# v2.net
KiCad netlist of a schematic drawn in EAGLE
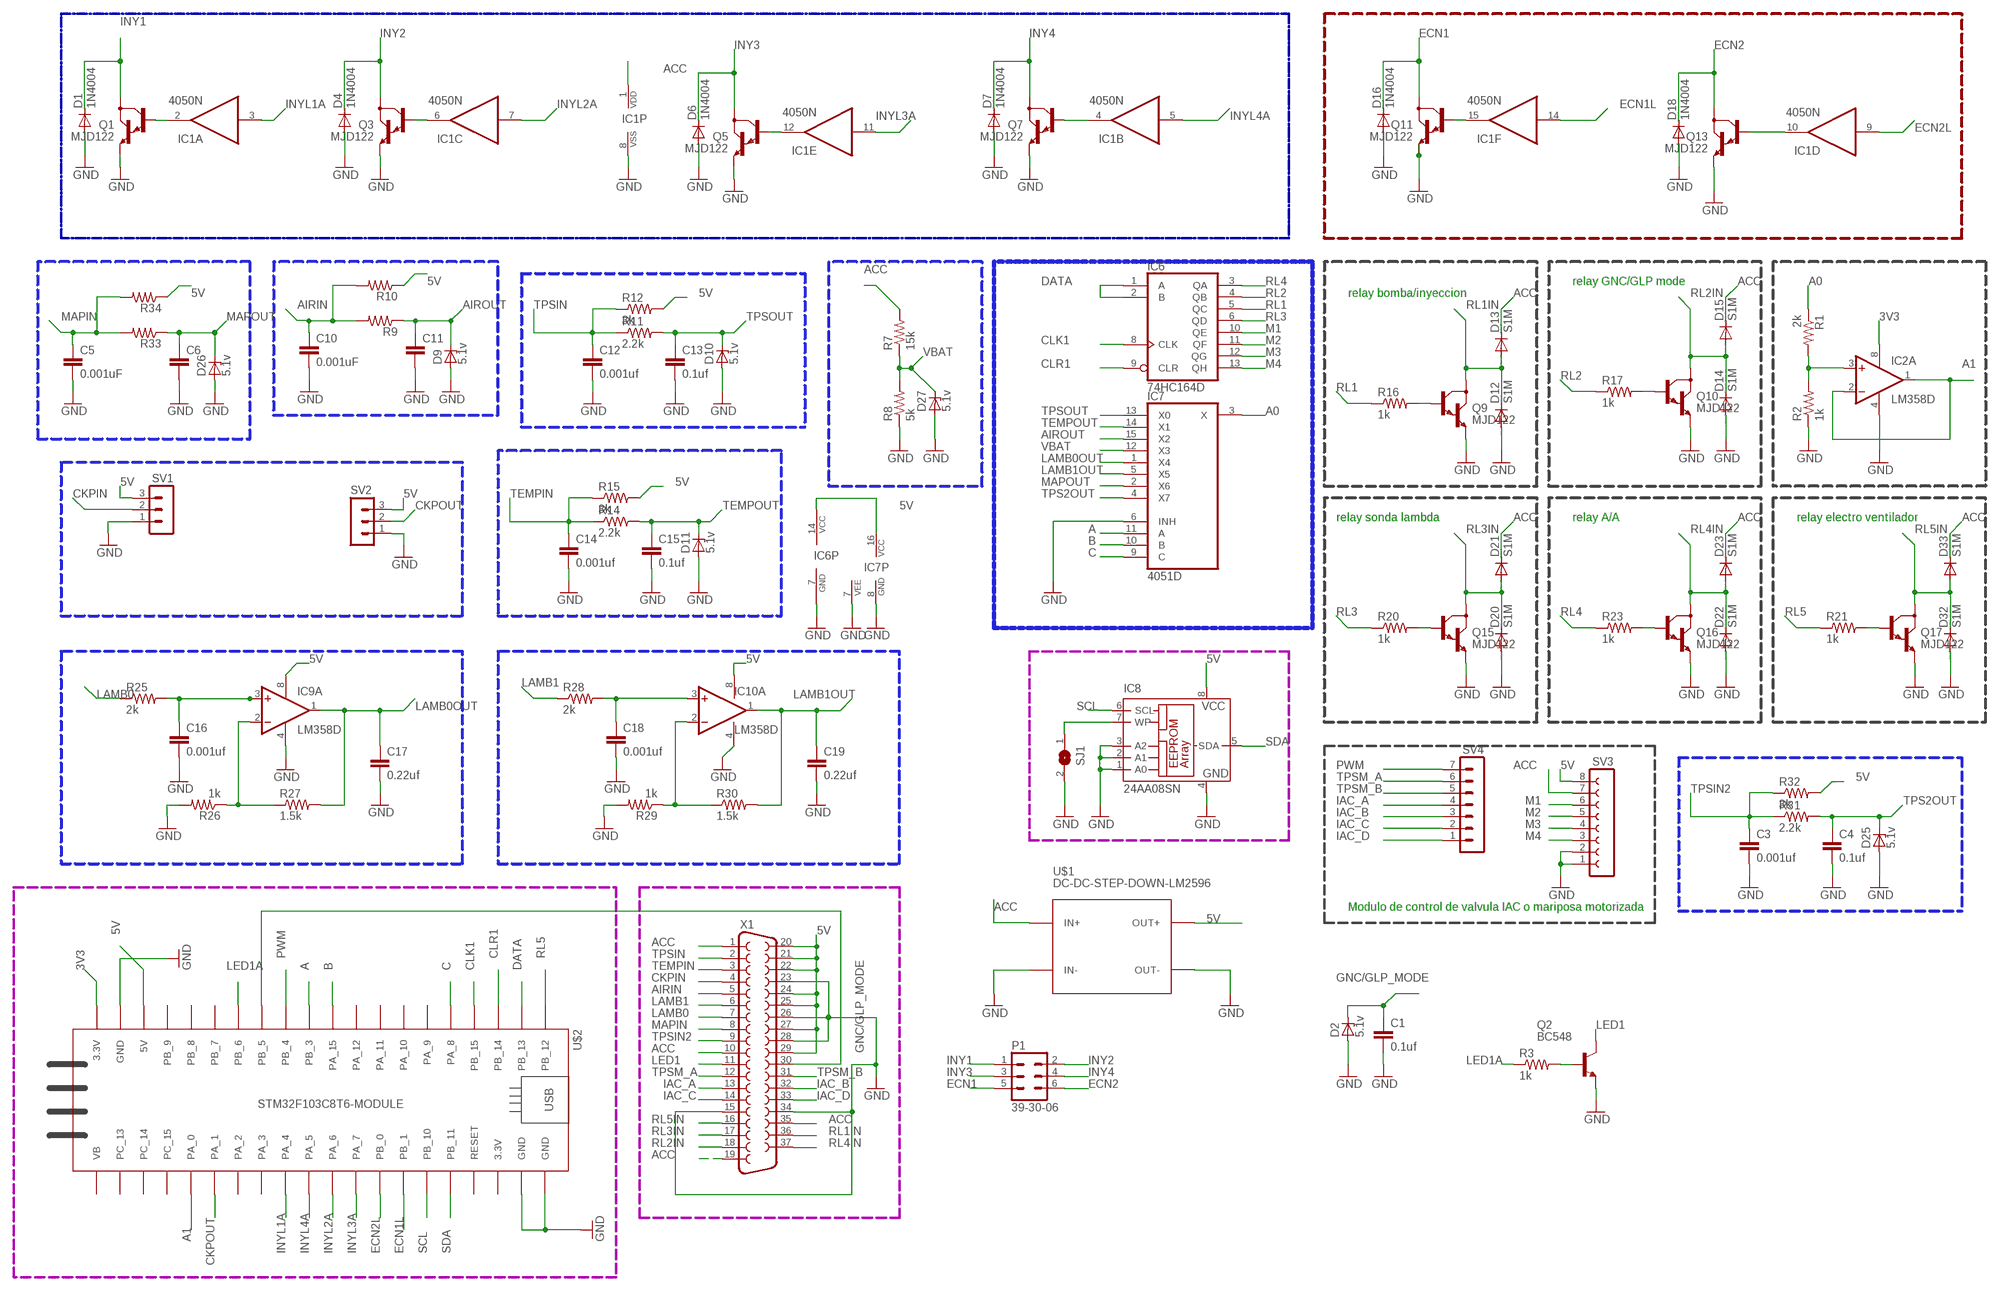
[diagram p0: schematic, sheet 1]

(export (version "E")
  (design (tool "Eeschema 10.0.6"))
  (components
    (comp (ref "C1")
      (value "0.1uf")
      (footprint "eagle-import:C025-025X050")
      (libsource (lib "eagle-import") (part "C-EU025-025X050"))
    )
    (comp (ref "C3")
      (value "0.001uf")
      (footprint "eagle-import:C025-025X050")
      (libsource (lib "eagle-import") (part "C-EU025-025X050"))
    )
    (comp (ref "C4")
      (value "0.1uf")
      (footprint "eagle-import:C025-025X050")
      (libsource (lib "eagle-import") (part "C-EU025-025X050"))
    )
    (comp (ref "C5")
      (value "0.001uF")
      (footprint "eagle-import:C025-025X050")
      (libsource (lib "eagle-import") (part "C-EU025-025X050"))
    )
    (comp (ref "C6")
      (value "C-EU025-025X050")
      (footprint "eagle-import:C025-025X050")
      (libsource (lib "eagle-import") (part "C-EU025-025X050"))
    )
    (comp (ref "C10")
      (value "0.001uF")
      (footprint "eagle-import:C025-025X050")
      (libsource (lib "eagle-import") (part "C-EU025-025X050"))
    )
    (comp (ref "C11")
      (value "C-EU025-025X050")
      (footprint "eagle-import:C025-025X050")
      (libsource (lib "eagle-import") (part "C-EU025-025X050"))
    )
    (comp (ref "C12")
      (value "0.001uf")
      (footprint "eagle-import:C025-025X050")
      (libsource (lib "eagle-import") (part "C-EU025-025X050"))
    )
    (comp (ref "C13")
      (value "0.1uf")
      (footprint "eagle-import:C025-025X050")
      (libsource (lib "eagle-import") (part "C-EU025-025X050"))
    )
    (comp (ref "C14")
      (value "0.001uf")
      (footprint "eagle-import:C025-025X050")
      (libsource (lib "eagle-import") (part "C-EU025-025X050"))
    )
    (comp (ref "C15")
      (value "0.1uf")
      (footprint "eagle-import:C025-025X050")
      (libsource (lib "eagle-import") (part "C-EU025-025X050"))
    )
    (comp (ref "C16")
      (value "0.001uf")
      (footprint "eagle-import:C025-025X050")
      (libsource (lib "eagle-import") (part "C-EU025-025X050"))
    )
    (comp (ref "C17")
      (value "0.22uf")
      (footprint "eagle-import:C025-025X050")
      (libsource (lib "eagle-import") (part "C-EU025-025X050"))
    )
    (comp (ref "C18")
      (value "0.001uf")
      (footprint "eagle-import:C025-025X050")
      (libsource (lib "eagle-import") (part "C-EU025-025X050"))
    )
    (comp (ref "C19")
      (value "0.22uf")
      (footprint "eagle-import:C025-025X050")
      (libsource (lib "eagle-import") (part "C-EU025-025X050"))
    )
    (comp (ref "D1")
      (value "1N4004")
      (footprint "eagle-import:DO41-10")
      (libsource (lib "eagle-import") (part "1N4004"))
    )
    (comp (ref "D2")
      (value "5.1v")
      (footprint "eagle-import:ZDIO-5")
      (libsource (lib "eagle-import") (part "ZENER-DIODEZD-5"))
    )
    (comp (ref "D4")
      (value "1N4004")
      (footprint "eagle-import:DO41-10")
      (libsource (lib "eagle-import") (part "1N4004"))
    )
    (comp (ref "D6")
      (value "1N4004")
      (footprint "eagle-import:DO41-10")
      (libsource (lib "eagle-import") (part "1N4004"))
    )
    (comp (ref "D7")
      (value "1N4004")
      (footprint "eagle-import:DO41-10")
      (libsource (lib "eagle-import") (part "1N4004"))
    )
    (comp (ref "D9")
      (value "5.1v")
      (footprint "eagle-import:ZDIO-5")
      (libsource (lib "eagle-import") (part "ZENER-DIODEZD-5"))
    )
    (comp (ref "D10")
      (value "5.1v")
      (footprint "eagle-import:ZDIO-5")
      (libsource (lib "eagle-import") (part "ZENER-DIODEZD-5"))
    )
    (comp (ref "D11")
      (value "5.1v")
      (footprint "eagle-import:ZDIO-5")
      (libsource (lib "eagle-import") (part "ZENER-DIODEZD-5"))
    )
    (comp (ref "D12")
      (value "S1M")
      (footprint "eagle-import:SMA")
      (libsource (lib "eagle-import") (part "S1M"))
    )
    (comp (ref "D13")
      (value "S1M")
      (footprint "eagle-import:SMA")
      (libsource (lib "eagle-import") (part "S1M"))
    )
    (comp (ref "D14")
      (value "S1M")
      (footprint "eagle-import:SMA")
      (libsource (lib "eagle-import") (part "S1M"))
    )
    (comp (ref "D15")
      (value "S1M")
      (footprint "eagle-import:SMA")
      (libsource (lib "eagle-import") (part "S1M"))
    )
    (comp (ref "D16")
      (value "1N4004")
      (footprint "eagle-import:DO41-10")
      (libsource (lib "eagle-import") (part "1N4004"))
    )
    (comp (ref "D18")
      (value "1N4004")
      (footprint "eagle-import:DO41-10")
      (libsource (lib "eagle-import") (part "1N4004"))
    )
    (comp (ref "D20")
      (value "S1M")
      (footprint "eagle-import:SMA")
      (libsource (lib "eagle-import") (part "S1M"))
    )
    (comp (ref "D21")
      (value "S1M")
      (footprint "eagle-import:SMA")
      (libsource (lib "eagle-import") (part "S1M"))
    )
    (comp (ref "D22")
      (value "S1M")
      (footprint "eagle-import:SMA")
      (libsource (lib "eagle-import") (part "S1M"))
    )
    (comp (ref "D23")
      (value "S1M")
      (footprint "eagle-import:SMA")
      (libsource (lib "eagle-import") (part "S1M"))
    )
    (comp (ref "D25")
      (value "5.1v")
      (footprint "eagle-import:ZDIO-5")
      (libsource (lib "eagle-import") (part "ZENER-DIODEZD-5"))
    )
    (comp (ref "D26")
      (value "5.1v")
      (footprint "eagle-import:ZDIO-5")
      (libsource (lib "eagle-import") (part "ZENER-DIODEZD-5"))
    )
    (comp (ref "D27")
      (value "5.1v")
      (footprint "eagle-import:ZDIO-5")
      (libsource (lib "eagle-import") (part "ZENER-DIODEZD-5"))
    )
    (comp (ref "D32")
      (value "S1M")
      (footprint "eagle-import:SMA")
      (libsource (lib "eagle-import") (part "S1M"))
    )
    (comp (ref "D33")
      (value "S1M")
      (footprint "eagle-import:SMA")
      (libsource (lib "eagle-import") (part "S1M"))
    )
    (comp (ref "IC1")
      (value "4050N")
      (footprint "eagle-import:DIL16")
      (libsource (lib "eagle-import") (part "4050N"))
    )
    (comp (ref "IC2")
      (value "LM358D")
      (footprint "eagle-import:SO08")
      (libsource (lib "eagle-import") (part "LM358D"))
    )
    (comp (ref "IC6")
      (value "74HC164D")
      (footprint "eagle-import:SO14")
      (libsource (lib "eagle-import") (part "74164DHC"))
    )
    (comp (ref "IC7")
      (value "4051D")
      (footprint "eagle-import:SO16")
      (libsource (lib "eagle-import") (part "4051D"))
    )
    (comp (ref "IC8")
      (value "24AA08SN")
      (footprint "eagle-import:SO-08")
      (fields (field (name "MF") "MICROCHIP") (field (name "MPN") "24AA08-I/SN"))
      (libsource (lib "eagle-import") (part "24SNAA08"))
    )
    (comp (ref "IC9")
      (value "LM358D")
      (footprint "eagle-import:SO08")
      (libsource (lib "eagle-import") (part "LM358D"))
    )
    (comp (ref "IC10")
      (value "LM358D")
      (footprint "eagle-import:SO08")
      (libsource (lib "eagle-import") (part "LM358D"))
    )
    (comp (ref "P1")
      (value "39-30-06")
      (footprint "eagle-import:39-30-_06_")
      (libsource (lib "eagle-import") (part "39-30-?06?"))
    )
    (comp (ref "Q1")
      (value "MJD122")
      (footprint "eagle-import:DPAK")
      (fields (field (name "MF") "STMicroelectronics"))
      (libsource (lib "eagle-import") (part "MJD122"))
    )
    (comp (ref "Q2")
      (value "BC548")
      (footprint "eagle-import:TO92-EBC")
      (libsource (lib "eagle-import") (part "BC548"))
    )
    (comp (ref "Q3")
      (value "MJD122")
      (footprint "eagle-import:DPAK")
      (fields (field (name "MF") "STMicroelectronics"))
      (libsource (lib "eagle-import") (part "MJD122"))
    )
    (comp (ref "Q5")
      (value "MJD122")
      (footprint "eagle-import:DPAK")
      (fields (field (name "MF") "STMicroelectronics"))
      (libsource (lib "eagle-import") (part "MJD122"))
    )
    (comp (ref "Q7")
      (value "MJD122")
      (footprint "eagle-import:DPAK")
      (fields (field (name "MF") "STMicroelectronics"))
      (libsource (lib "eagle-import") (part "MJD122"))
    )
    (comp (ref "Q9")
      (value "MJD122")
      (footprint "eagle-import:DPAK")
      (fields (field (name "MF") "STMicroelectronics"))
      (libsource (lib "eagle-import") (part "MJD122"))
    )
    (comp (ref "Q10")
      (value "MJD122")
      (footprint "eagle-import:DPAK")
      (fields (field (name "MF") "STMicroelectronics"))
      (libsource (lib "eagle-import") (part "MJD122"))
    )
    (comp (ref "Q11")
      (value "MJD122")
      (footprint "eagle-import:DPAK")
      (fields (field (name "MF") "STMicroelectronics"))
      (libsource (lib "eagle-import") (part "MJD122"))
    )
    (comp (ref "Q13")
      (value "MJD122")
      (footprint "eagle-import:DPAK")
      (fields (field (name "MF") "STMicroelectronics"))
      (libsource (lib "eagle-import") (part "MJD122"))
    )
    (comp (ref "Q15")
      (value "MJD122")
      (footprint "eagle-import:DPAK")
      (fields (field (name "MF") "STMicroelectronics"))
      (libsource (lib "eagle-import") (part "MJD122"))
    )
    (comp (ref "Q16")
      (value "MJD122")
      (footprint "eagle-import:DPAK")
      (fields (field (name "MF") "STMicroelectronics"))
      (libsource (lib "eagle-import") (part "MJD122"))
    )
    (comp (ref "Q17")
      (value "MJD122")
      (footprint "eagle-import:DPAK")
      (fields (field (name "MF") "STMicroelectronics"))
      (libsource (lib "eagle-import") (part "MJD122"))
    )
    (comp (ref "R1")
      (value "2k")
      (footprint "eagle-import:0204_5")
      (libsource (lib "eagle-import") (part "R-US_0204/5"))
    )
    (comp (ref "R2")
      (value "1k")
      (footprint "eagle-import:0204_5")
      (libsource (lib "eagle-import") (part "R-US_0204/5"))
    )
    (comp (ref "R3")
      (value "1k")
      (footprint "eagle-import:0204_5")
      (libsource (lib "eagle-import") (part "R-US_0204/5"))
    )
    (comp (ref "R7")
      (value "15k")
      (footprint "eagle-import:0204_5")
      (libsource (lib "eagle-import") (part "R-US_0204/5"))
    )
    (comp (ref "R8")
      (value "5k")
      (footprint "eagle-import:0204_5")
      (libsource (lib "eagle-import") (part "R-US_0204/5"))
    )
    (comp (ref "R9")
      (value "R-US_0204/5")
      (footprint "eagle-import:0204_5")
      (libsource (lib "eagle-import") (part "R-US_0204/5"))
    )
    (comp (ref "R10")
      (value "R-US_0204/5")
      (footprint "eagle-import:0204_5")
      (libsource (lib "eagle-import") (part "R-US_0204/5"))
    )
    (comp (ref "R11")
      (value "2.2k")
      (footprint "eagle-import:0204_5")
      (libsource (lib "eagle-import") (part "R-US_0204/5"))
    )
    (comp (ref "R12")
      (value "3k")
      (footprint "eagle-import:0204_5")
      (libsource (lib "eagle-import") (part "R-US_0204/5"))
    )
    (comp (ref "R14")
      (value "2.2k")
      (footprint "eagle-import:0204_5")
      (libsource (lib "eagle-import") (part "R-US_0204/5"))
    )
    (comp (ref "R15")
      (value "3k")
      (footprint "eagle-import:0204_5")
      (libsource (lib "eagle-import") (part "R-US_0204/5"))
    )
    (comp (ref "R16")
      (value "1k")
      (footprint "eagle-import:0204_5")
      (libsource (lib "eagle-import") (part "R-US_0204/5"))
    )
    (comp (ref "R17")
      (value "1k")
      (footprint "eagle-import:0204_5")
      (libsource (lib "eagle-import") (part "R-US_0204/5"))
    )
    (comp (ref "R20")
      (value "1k")
      (footprint "eagle-import:0204_5")
      (libsource (lib "eagle-import") (part "R-US_0204/5"))
    )
    (comp (ref "R21")
      (value "1k")
      (footprint "eagle-import:0204_5")
      (libsource (lib "eagle-import") (part "R-US_0204/5"))
    )
    (comp (ref "R23")
      (value "1k")
      (footprint "eagle-import:0204_5")
      (libsource (lib "eagle-import") (part "R-US_0204/5"))
    )
    (comp (ref "R25")
      (value "2k")
      (footprint "eagle-import:0204_5")
      (libsource (lib "eagle-import") (part "R-US_0204/5"))
    )
    (comp (ref "R26")
      (value "1k")
      (footprint "eagle-import:0204_5")
      (libsource (lib "eagle-import") (part "R-US_0204/5"))
    )
    (comp (ref "R27")
      (value "1.5k")
      (footprint "eagle-import:0204_5")
      (libsource (lib "eagle-import") (part "R-US_0204/5"))
    )
    (comp (ref "R28")
      (value "2k")
      (footprint "eagle-import:0204_5")
      (libsource (lib "eagle-import") (part "R-US_0204/5"))
    )
    (comp (ref "R29")
      (value "1k")
      (footprint "eagle-import:0204_5")
      (libsource (lib "eagle-import") (part "R-US_0204/5"))
    )
    (comp (ref "R30")
      (value "1.5k")
      (footprint "eagle-import:0204_5")
      (libsource (lib "eagle-import") (part "R-US_0204/5"))
    )
    (comp (ref "R31")
      (value "2.2k")
      (footprint "eagle-import:0204_5")
      (libsource (lib "eagle-import") (part "R-US_0204/5"))
    )
    (comp (ref "R32")
      (value "3k")
      (footprint "eagle-import:0204_5")
      (libsource (lib "eagle-import") (part "R-US_0204/5"))
    )
    (comp (ref "R33")
      (value "R-US_0204/5")
      (footprint "eagle-import:0204_5")
      (libsource (lib "eagle-import") (part "R-US_0204/5"))
    )
    (comp (ref "R34")
      (value "R-US_0204/5")
      (footprint "eagle-import:0204_5")
      (libsource (lib "eagle-import") (part "R-US_0204/5"))
    )
    (comp (ref "SJ1")
      (value "SJW")
      (footprint "eagle-import:SJW")
      (libsource (lib "eagle-import") (part "SJW"))
    )
    (comp (ref "SV1")
      (value "MA03-1")
      (footprint "eagle-import:MA03-1")
      (libsource (lib "eagle-import") (part "MA03-1"))
    )
    (comp (ref "SV2")
      (value "MA03-1")
      (footprint "eagle-import:MA03-1")
      (libsource (lib "eagle-import") (part "MA03-1"))
    )
    (comp (ref "SV3")
      (value "FE08-1")
      (footprint "eagle-import:FE08")
      (libsource (lib "eagle-import") (part "FE08-1"))
    )
    (comp (ref "SV4")
      (value "MA07-1")
      (footprint "eagle-import:MA07-1")
      (libsource (lib "eagle-import") (part "MA07-1"))
    )
    (comp (ref "U$1")
      (value "DC-DC-STEP-DOWN-LM2596")
      (footprint "eagle-import:DC-DC-STEP-DOWN-LM2596")
      (libsource (lib "eagle-import") (part "DC-DC-STEP-DOWN-LM2596"))
    )
    (comp (ref "U$2")
      (value "STM32F103C8T6-MODULE")
      (footprint "eagle-import:STM32F103C8T6-MODULE")
      (libsource (lib "eagle-import") (part "STM32F103C8T6-MODULE"))
    )
    (comp (ref "X1")
      (value "F37HP")
      (footprint "eagle-import:F37HP")
      (libsource (lib "eagle-import") (part "F37HP"))
    )
  )
  (nets
    (net (code "1") (name "/3V3") (class "Default")
      (node (ref "IC2") (pin "8") (pinfunction "V+_8") (pintype "power_in"))
      (node (ref "U$2") (pin "3.3V_1") (pinfunction "3.3V_3.3V_1") (pintype "bidirectional"))
    )
    (net (code "2") (name "/5V") (class "Default")
      (node (ref "IC10") (pin "8") (pinfunction "V+_8") (pintype "power_in"))
      (node (ref "IC6") (pin "14") (pinfunction "VCC_14") (pintype "power_in"))
      (node (ref "IC7") (pin "16") (pinfunction "VCC_16") (pintype "power_in"))
      (node (ref "IC8") (pin "8") (pinfunction "VCC_8") (pintype "power_in"))
      (node (ref "IC9") (pin "8") (pinfunction "V+_8") (pintype "power_in"))
      (node (ref "R10") (pin "1") (pinfunction "1_1") (pintype "passive"))
      (node (ref "R12") (pin "2") (pinfunction "2_2") (pintype "passive"))
      (node (ref "R15") (pin "2") (pinfunction "2_2") (pintype "passive"))
      (node (ref "R32") (pin "2") (pinfunction "2_2") (pintype "passive"))
      (node (ref "R34") (pin "1") (pinfunction "1_1") (pintype "passive"))
      (node (ref "SV1") (pin "3") (pinfunction "3_3") (pintype "passive"))
      (node (ref "SV2") (pin "3") (pinfunction "3_3") (pintype "passive"))
      (node (ref "SV3") (pin "8") (pinfunction "8_8") (pintype "passive"))
      (node (ref "U$1") (pin "OUT+") (pinfunction "OUT+_OUT+") (pintype "bidirectional"))
      (node (ref "U$2") (pin "5V") (pinfunction "5V_5V") (pintype "bidirectional"))
      (node (ref "X1") (pin "20") (pinfunction "20_20") (pintype "passive"))
      (node (ref "X1") (pin "21") (pinfunction "21_21") (pintype "passive"))
      (node (ref "X1") (pin "22") (pinfunction "22_22") (pintype "passive"))
      (node (ref "X1") (pin "24") (pinfunction "24_24") (pintype "passive"))
      (node (ref "X1") (pin "25") (pinfunction "25_25") (pintype "passive"))
      (node (ref "X1") (pin "27") (pinfunction "27_27") (pintype "passive"))
      (node (ref "X1") (pin "29") (pinfunction "29_29") (pintype "passive"))
    )
    (net (code "3") (name "/A") (class "Default")
      (node (ref "IC7") (pin "11") (pinfunction "A_11") (pintype "input"))
      (node (ref "U$2") (pin "PB_3") (pinfunction "PB_3_PB_3") (pintype "bidirectional"))
    )
    (net (code "4") (name "/A0") (class "Default")
      (node (ref "IC7") (pin "3") (pinfunction "X_3") (pintype "bidirectional"))
      (node (ref "R1") (pin "1") (pinfunction "1_1") (pintype "passive"))
    )
    (net (code "5") (name "/A1") (class "Default")
      (node (ref "IC2") (pin "1") (pinfunction "OUT_1") (pintype "output"))
      (node (ref "IC2") (pin "2") (pinfunction "-IN_2") (pintype "input"))
      (node (ref "U$2") (pin "PA_0") (pinfunction "PA_0_PA_0") (pintype "bidirectional"))
    )
    (net (code "6") (name "/ACC") (class "Default")
      (node (ref "D13") (pin "C") (pinfunction "C_C") (pintype "passive"))
      (node (ref "D15") (pin "C") (pinfunction "C_C") (pintype "passive"))
      (node (ref "D21") (pin "C") (pinfunction "C_C") (pintype "passive"))
      (node (ref "D23") (pin "C") (pinfunction "C_C") (pintype "passive"))
      (node (ref "D33") (pin "C") (pinfunction "C_C") (pintype "passive"))
      (node (ref "IC1") (pin "1") (pinfunction "VDD_1") (pintype "power_in"))
      (node (ref "R7") (pin "2") (pinfunction "2_2") (pintype "passive"))
      (node (ref "SV3") (pin "7") (pinfunction "7_7") (pintype "passive"))
      (node (ref "U$1") (pin "IN+") (pinfunction "IN+_IN+") (pintype "bidirectional"))
      (node (ref "X1") (pin "1") (pinfunction "1_1") (pintype "passive"))
      (node (ref "X1") (pin "10") (pinfunction "10_10") (pintype "passive"))
      (node (ref "X1") (pin "19") (pinfunction "19_19") (pintype "passive"))
      (node (ref "X1") (pin "35") (pinfunction "35_35") (pintype "passive"))
    )
    (net (code "7") (name "/AIRIN") (class "Default")
      (node (ref "C10") (pin "1") (pinfunction "1_1") (pintype "passive"))
      (node (ref "R10") (pin "2") (pinfunction "2_2") (pintype "passive"))
      (node (ref "R9") (pin "2") (pinfunction "2_2") (pintype "passive"))
      (node (ref "X1") (pin "5") (pinfunction "5_5") (pintype "passive"))
    )
    (net (code "8") (name "/AIROUT") (class "Default")
      (node (ref "C11") (pin "1") (pinfunction "1_1") (pintype "passive"))
      (node (ref "D9") (pin "C") (pinfunction "C_C") (pintype "passive"))
      (node (ref "IC7") (pin "15") (pinfunction "X2_15") (pintype "bidirectional"))
      (node (ref "R9") (pin "1") (pinfunction "1_1") (pintype "passive"))
    )
    (net (code "9") (name "/B") (class "Default")
      (node (ref "IC7") (pin "10") (pinfunction "B_10") (pintype "input"))
      (node (ref "U$2") (pin "PA_15") (pinfunction "PA_15_PA_15") (pintype "bidirectional"))
    )
    (net (code "10") (name "/C") (class "Default")
      (node (ref "IC7") (pin "9") (pinfunction "C_9") (pintype "input"))
      (node (ref "U$2") (pin "PA_8") (pinfunction "PA_8_PA_8") (pintype "bidirectional"))
    )
    (net (code "11") (name "/CKPIN") (class "Default")
      (node (ref "SV1") (pin "2") (pinfunction "2_2") (pintype "passive"))
      (node (ref "X1") (pin "4") (pinfunction "4_4") (pintype "passive"))
    )
    (net (code "12") (name "/CKPOUT") (class "Default")
      (node (ref "SV2") (pin "2") (pinfunction "2_2") (pintype "passive"))
      (node (ref "U$2") (pin "PA_1") (pinfunction "PA_1_PA_1") (pintype "bidirectional"))
    )
    (net (code "13") (name "/CLK1") (class "Default")
      (node (ref "IC6") (pin "8") (pinfunction "CLK_8") (pintype "input"))
      (node (ref "U$2") (pin "PB_15") (pinfunction "PB_15_PB_15") (pintype "bidirectional"))
    )
    (net (code "14") (name "/CLR1") (class "Default")
      (node (ref "IC6") (pin "9") (pinfunction "CLR_9") (pintype "input"))
      (node (ref "U$2") (pin "PB_14") (pinfunction "PB_14_PB_14") (pintype "bidirectional"))
    )
    (net (code "15") (name "/DATA") (class "Default")
      (node (ref "IC6") (pin "1") (pinfunction "A_1") (pintype "input"))
      (node (ref "IC6") (pin "2") (pinfunction "B_2") (pintype "input"))
      (node (ref "U$2") (pin "PB_13") (pinfunction "PB_13_PB_13") (pintype "bidirectional"))
    )
    (net (code "16") (name "/ECN1") (class "Default")
      (node (ref "D16") (pin "C") (pinfunction "C_C") (pintype "passive"))
      (node (ref "P1") (pin "5") (pinfunction "5_5") (pintype "passive"))
      (node (ref "Q11") (pin "4") (pinfunction "C_4") (pintype "passive"))
    )
    (net (code "17") (name "/ECN1L") (class "Default")
      (node (ref "IC1") (pin "14") (pinfunction "I_14") (pintype "input"))
      (node (ref "U$2") (pin "PB_1") (pinfunction "PB_1_PB_1") (pintype "bidirectional"))
    )
    (net (code "18") (name "/ECN2") (class "Default")
      (node (ref "D18") (pin "C") (pinfunction "C_C") (pintype "passive"))
      (node (ref "P1") (pin "6") (pinfunction "6_6") (pintype "passive"))
      (node (ref "Q13") (pin "4") (pinfunction "C_4") (pintype "passive"))
    )
    (net (code "19") (name "/ECN2L") (class "Default")
      (node (ref "IC1") (pin "9") (pinfunction "I_9") (pintype "input"))
      (node (ref "U$2") (pin "PB_0") (pinfunction "PB_0_PB_0") (pintype "bidirectional"))
    )
    (net (code "20") (name "/GNC{slash}GLP_MODE") (class "Default")
      (node (ref "C1") (pin "1") (pinfunction "1_1") (pintype "passive"))
      (node (ref "D2") (pin "C") (pinfunction "C_C") (pintype "passive"))
      (node (ref "U$2") (pin "PB_5") (pinfunction "PB_5_PB_5") (pintype "bidirectional"))
      (node (ref "X1") (pin "30") (pinfunction "30_30") (pintype "passive"))
    )
    (net (code "21") (name "/IAC_A") (class "Default")
      (node (ref "SV4") (pin "4") (pinfunction "4_4") (pintype "passive"))
      (node (ref "X1") (pin "13") (pinfunction "13_13") (pintype "passive"))
    )
    (net (code "22") (name "/IAC_B") (class "Default")
      (node (ref "SV4") (pin "3") (pinfunction "3_3") (pintype "passive"))
      (node (ref "X1") (pin "32") (pinfunction "32_32") (pintype "passive"))
    )
    (net (code "23") (name "/IAC_C") (class "Default")
      (node (ref "SV4") (pin "2") (pinfunction "2_2") (pintype "passive"))
      (node (ref "X1") (pin "14") (pinfunction "14_14") (pintype "passive"))
    )
    (net (code "24") (name "/IAC_D") (class "Default")
      (node (ref "SV4") (pin "1") (pinfunction "1_1") (pintype "passive"))
      (node (ref "X1") (pin "33") (pinfunction "33_33") (pintype "passive"))
    )
    (net (code "25") (name "/INY1") (class "Default")
      (node (ref "D1") (pin "C") (pinfunction "C_C") (pintype "passive"))
      (node (ref "P1") (pin "1") (pinfunction "1_1") (pintype "passive"))
      (node (ref "Q1") (pin "4") (pinfunction "C_4") (pintype "passive"))
    )
    (net (code "26") (name "/INY2") (class "Default")
      (node (ref "D4") (pin "C") (pinfunction "C_C") (pintype "passive"))
      (node (ref "P1") (pin "2") (pinfunction "2_2") (pintype "passive"))
      (node (ref "Q3") (pin "4") (pinfunction "C_4") (pintype "passive"))
    )
    (net (code "27") (name "/INY3") (class "Default")
      (node (ref "D6") (pin "C") (pinfunction "C_C") (pintype "passive"))
      (node (ref "P1") (pin "3") (pinfunction "3_3") (pintype "passive"))
      (node (ref "Q5") (pin "4") (pinfunction "C_4") (pintype "passive"))
    )
    (net (code "28") (name "/INY4") (class "Default")
      (node (ref "D7") (pin "C") (pinfunction "C_C") (pintype "passive"))
      (node (ref "P1") (pin "4") (pinfunction "4_4") (pintype "passive"))
      (node (ref "Q7") (pin "4") (pinfunction "C_4") (pintype "passive"))
    )
    (net (code "29") (name "/INYL1A") (class "Default")
      (node (ref "IC1") (pin "3") (pinfunction "I_3") (pintype "input"))
      (node (ref "U$2") (pin "PA_4") (pinfunction "PA_4_PA_4") (pintype "bidirectional"))
    )
    (net (code "30") (name "/INYL2A") (class "Default")
      (node (ref "IC1") (pin "7") (pinfunction "I_7") (pintype "input"))
      (node (ref "U$2") (pin "PA_6") (pinfunction "PA_6_PA_6") (pintype "bidirectional"))
    )
    (net (code "31") (name "/INYL3A") (class "Default")
      (node (ref "IC1") (pin "11") (pinfunction "I_11") (pintype "input"))
      (node (ref "U$2") (pin "PA_7") (pinfunction "PA_7_PA_7") (pintype "bidirectional"))
    )
    (net (code "32") (name "/INYL4A") (class "Default")
      (node (ref "IC1") (pin "5") (pinfunction "I_5") (pintype "input"))
      (node (ref "U$2") (pin "PA_5") (pinfunction "PA_5_PA_5") (pintype "bidirectional"))
    )
    (net (code "33") (name "/LAMB0") (class "Default")
      (node (ref "R25") (pin "1") (pinfunction "1_1") (pintype "passive"))
      (node (ref "X1") (pin "7") (pinfunction "7_7") (pintype "passive"))
    )
    (net (code "34") (name "/LAMB0OUT") (class "Default")
      (node (ref "C17") (pin "1") (pinfunction "1_1") (pintype "passive"))
      (node (ref "IC7") (pin "1") (pinfunction "X4_1") (pintype "bidirectional"))
      (node (ref "IC9") (pin "1") (pinfunction "OUT_1") (pintype "output"))
      (node (ref "R27") (pin "2") (pinfunction "2_2") (pintype "passive"))
    )
    (net (code "35") (name "/LAMB1") (class "Default")
      (node (ref "R28") (pin "1") (pinfunction "1_1") (pintype "passive"))
      (node (ref "X1") (pin "6") (pinfunction "6_6") (pintype "passive"))
    )
    (net (code "36") (name "/LAMB1OUT") (class "Default")
      (node (ref "C19") (pin "1") (pinfunction "1_1") (pintype "passive"))
      (node (ref "IC10") (pin "1") (pinfunction "OUT_1") (pintype "output"))
      (node (ref "IC7") (pin "5") (pinfunction "X5_5") (pintype "bidirectional"))
      (node (ref "R30") (pin "2") (pinfunction "2_2") (pintype "passive"))
    )
    (net (code "37") (name "/LED1") (class "Default")
      (node (ref "Q2") (pin "C") (pinfunction "C_C") (pintype "passive"))
      (node (ref "X1") (pin "11") (pinfunction "11_11") (pintype "passive"))
    )
    (net (code "38") (name "/LED1A") (class "Default")
      (node (ref "R3") (pin "1") (pinfunction "1_1") (pintype "passive"))
      (node (ref "U$2") (pin "PB_6") (pinfunction "PB_6_PB_6") (pintype "bidirectional"))
    )
    (net (code "39") (name "/M1") (class "Default")
      (node (ref "IC6") (pin "10") (pinfunction "QE_10") (pintype "output"))
      (node (ref "SV3") (pin "6") (pinfunction "6_6") (pintype "passive"))
    )
    (net (code "40") (name "/M2") (class "Default")
      (node (ref "IC6") (pin "11") (pinfunction "QF_11") (pintype "output"))
      (node (ref "SV3") (pin "5") (pinfunction "5_5") (pintype "passive"))
    )
    (net (code "41") (name "/M3") (class "Default")
      (node (ref "IC6") (pin "12") (pinfunction "QG_12") (pintype "output"))
      (node (ref "SV3") (pin "4") (pinfunction "4_4") (pintype "passive"))
    )
    (net (code "42") (name "/M4") (class "Default")
      (node (ref "IC6") (pin "13") (pinfunction "QH_13") (pintype "output"))
      (node (ref "SV3") (pin "3") (pinfunction "3_3") (pintype "passive"))
    )
    (net (code "43") (name "/MAPIN") (class "Default")
      (node (ref "C5") (pin "1") (pinfunction "1_1") (pintype "passive"))
      (node (ref "R33") (pin "2") (pinfunction "2_2") (pintype "passive"))
      (node (ref "R34") (pin "2") (pinfunction "2_2") (pintype "passive"))
      (node (ref "X1") (pin "8") (pinfunction "8_8") (pintype "passive"))
    )
    (net (code "44") (name "/MAPOUT") (class "Default")
      (node (ref "C6") (pin "1") (pinfunction "1_1") (pintype "passive"))
      (node (ref "D26") (pin "C") (pinfunction "C_C") (pintype "passive"))
      (node (ref "IC7") (pin "2") (pinfunction "X6_2") (pintype "bidirectional"))
      (node (ref "R33") (pin "1") (pinfunction "1_1") (pintype "passive"))
    )
    (net (code "45") (name "/PWM") (class "Default")
      (node (ref "SV4") (pin "7") (pinfunction "7_7") (pintype "passive"))
      (node (ref "U$2") (pin "PB_4") (pinfunction "PB_4_PB_4") (pintype "bidirectional"))
    )
    (net (code "46") (name "/RL1") (class "Default")
      (node (ref "IC6") (pin "5") (pinfunction "QC_5") (pintype "output"))
      (node (ref "R16") (pin "1") (pinfunction "1_1") (pintype "passive"))
    )
    (net (code "47") (name "/RL1IN") (class "Default")
      (node (ref "D12") (pin "C") (pinfunction "C_C") (pintype "passive"))
      (node (ref "D13") (pin "A") (pinfunction "A_A") (pintype "passive"))
      (node (ref "Q9") (pin "4") (pinfunction "C_4") (pintype "passive"))
      (node (ref "X1") (pin "36") (pinfunction "36_36") (pintype "passive"))
    )
    (net (code "48") (name "/RL2") (class "Default")
      (node (ref "IC6") (pin "4") (pinfunction "QB_4") (pintype "output"))
      (node (ref "R17") (pin "1") (pinfunction "1_1") (pintype "passive"))
    )
    (net (code "49") (name "/RL2IN") (class "Default")
      (node (ref "D14") (pin "C") (pinfunction "C_C") (pintype "passive"))
      (node (ref "D15") (pin "A") (pinfunction "A_A") (pintype "passive"))
      (node (ref "Q10") (pin "4") (pinfunction "C_4") (pintype "passive"))
      (node (ref "X1") (pin "18") (pinfunction "18_18") (pintype "passive"))
    )
    (net (code "50") (name "/RL3") (class "Default")
      (node (ref "IC6") (pin "6") (pinfunction "QD_6") (pintype "output"))
      (node (ref "R20") (pin "1") (pinfunction "1_1") (pintype "passive"))
    )
    (net (code "51") (name "/RL3IN") (class "Default")
      (node (ref "D20") (pin "C") (pinfunction "C_C") (pintype "passive"))
      (node (ref "D21") (pin "A") (pinfunction "A_A") (pintype "passive"))
      (node (ref "Q15") (pin "4") (pinfunction "C_4") (pintype "passive"))
      (node (ref "X1") (pin "17") (pinfunction "17_17") (pintype "passive"))
    )
    (net (code "52") (name "/RL4") (class "Default")
      (node (ref "IC6") (pin "3") (pinfunction "QA_3") (pintype "output"))
      (node (ref "R23") (pin "1") (pinfunction "1_1") (pintype "passive"))
    )
    (net (code "53") (name "/RL4IN") (class "Default")
      (node (ref "D22") (pin "C") (pinfunction "C_C") (pintype "passive"))
      (node (ref "D23") (pin "A") (pinfunction "A_A") (pintype "passive"))
      (node (ref "Q16") (pin "4") (pinfunction "C_4") (pintype "passive"))
      (node (ref "X1") (pin "37") (pinfunction "37_37") (pintype "passive"))
    )
    (net (code "54") (name "/RL5") (class "Default")
      (node (ref "R21") (pin "1") (pinfunction "1_1") (pintype "passive"))
      (node (ref "U$2") (pin "PB_12") (pinfunction "PB_12_PB_12") (pintype "bidirectional"))
    )
    (net (code "55") (name "/RL5IN") (class "Default")
      (node (ref "D32") (pin "C") (pinfunction "C_C") (pintype "passive"))
      (node (ref "D33") (pin "A") (pinfunction "A_A") (pintype "passive"))
      (node (ref "Q17") (pin "4") (pinfunction "C_4") (pintype "passive"))
      (node (ref "X1") (pin "16") (pinfunction "16_16") (pintype "passive"))
    )
    (net (code "56") (name "/SCL") (class "Default")
      (node (ref "IC8") (pin "6") (pinfunction "SCL_6") (pintype "input"))
      (node (ref "U$2") (pin "PB_10") (pinfunction "PB_10_PB_10") (pintype "bidirectional"))
    )
    (net (code "57") (name "/SDA") (class "Default")
      (node (ref "IC8") (pin "5") (pinfunction "SDA_5") (pintype "bidirectional"))
      (node (ref "U$2") (pin "PB_11") (pinfunction "PB_11_PB_11") (pintype "bidirectional"))
    )
    (net (code "58") (name "/TEMPIN") (class "Default")
      (node (ref "C14") (pin "1") (pinfunction "1_1") (pintype "passive"))
      (node (ref "R14") (pin "1") (pinfunction "1_1") (pintype "passive"))
      (node (ref "R15") (pin "1") (pinfunction "1_1") (pintype "passive"))
      (node (ref "X1") (pin "3") (pinfunction "3_3") (pintype "passive"))
    )
    (net (code "59") (name "/TEMPOUT") (class "Default")
      (node (ref "C15") (pin "1") (pinfunction "1_1") (pintype "passive"))
      (node (ref "D11") (pin "C") (pinfunction "C_C") (pintype "passive"))
      (node (ref "IC7") (pin "14") (pinfunction "X1_14") (pintype "bidirectional"))
      (node (ref "R14") (pin "2") (pinfunction "2_2") (pintype "passive"))
    )
    (net (code "60") (name "/TPS2OUT") (class "Default")
      (node (ref "C4") (pin "1") (pinfunction "1_1") (pintype "passive"))
      (node (ref "D25") (pin "C") (pinfunction "C_C") (pintype "passive"))
      (node (ref "IC7") (pin "4") (pinfunction "X7_4") (pintype "bidirectional"))
      (node (ref "R31") (pin "2") (pinfunction "2_2") (pintype "passive"))
    )
    (net (code "61") (name "/TPSIN") (class "Default")
      (node (ref "C12") (pin "1") (pinfunction "1_1") (pintype "passive"))
      (node (ref "R11") (pin "1") (pinfunction "1_1") (pintype "passive"))
      (node (ref "R12") (pin "1") (pinfunction "1_1") (pintype "passive"))
      (node (ref "X1") (pin "2") (pinfunction "2_2") (pintype "passive"))
    )
    (net (code "62") (name "/TPSIN2") (class "Default")
      (node (ref "C3") (pin "1") (pinfunction "1_1") (pintype "passive"))
      (node (ref "R31") (pin "1") (pinfunction "1_1") (pintype "passive"))
      (node (ref "R32") (pin "1") (pinfunction "1_1") (pintype "passive"))
      (node (ref "X1") (pin "9") (pinfunction "9_9") (pintype "passive"))
    )
    (net (code "63") (name "/TPSM_A") (class "Default")
      (node (ref "SV4") (pin "6") (pinfunction "6_6") (pintype "passive"))
      (node (ref "X1") (pin "12") (pinfunction "12_12") (pintype "passive"))
    )
    (net (code "64") (name "/TPSM_B") (class "Default")
      (node (ref "SV4") (pin "5") (pinfunction "5_5") (pintype "passive"))
      (node (ref "X1") (pin "31") (pinfunction "31_31") (pintype "passive"))
    )
    (net (code "65") (name "/TPSOUT") (class "Default")
      (node (ref "C13") (pin "1") (pinfunction "1_1") (pintype "passive"))
      (node (ref "D10") (pin "C") (pinfunction "C_C") (pintype "passive"))
      (node (ref "IC7") (pin "13") (pinfunction "X0_13") (pintype "bidirectional"))
      (node (ref "R11") (pin "2") (pinfunction "2_2") (pintype "passive"))
    )
    (net (code "66") (name "/VBAT") (class "Default")
      (node (ref "D27") (pin "C") (pinfunction "C_C") (pintype "passive"))
      (node (ref "IC7") (pin "12") (pinfunction "X3_12") (pintype "bidirectional"))
      (node (ref "R7") (pin "1") (pinfunction "1_1") (pintype "passive"))
      (node (ref "R8") (pin "2") (pinfunction "2_2") (pintype "passive"))
    )
    (net (code "67") (name "GND") (class "Default")
      (node (ref "C1") (pin "2") (pinfunction "2_2") (pintype "passive"))
      (node (ref "C10") (pin "2") (pinfunction "2_2") (pintype "passive"))
      (node (ref "C11") (pin "2") (pinfunction "2_2") (pintype "passive"))
      (node (ref "C12") (pin "2") (pinfunction "2_2") (pintype "passive"))
      (node (ref "C13") (pin "2") (pinfunction "2_2") (pintype "passive"))
      (node (ref "C14") (pin "2") (pinfunction "2_2") (pintype "passive"))
      (node (ref "C15") (pin "2") (pinfunction "2_2") (pintype "passive"))
      (node (ref "C16") (pin "2") (pinfunction "2_2") (pintype "passive"))
      (node (ref "C17") (pin "2") (pinfunction "2_2") (pintype "passive"))
      (node (ref "C18") (pin "2") (pinfunction "2_2") (pintype "passive"))
      (node (ref "C19") (pin "2") (pinfunction "2_2") (pintype "passive"))
      (node (ref "C3") (pin "2") (pinfunction "2_2") (pintype "passive"))
      (node (ref "C4") (pin "2") (pinfunction "2_2") (pintype "passive"))
      (node (ref "C5") (pin "2") (pinfunction "2_2") (pintype "passive"))
      (node (ref "C6") (pin "2") (pinfunction "2_2") (pintype "passive"))
      (node (ref "D1") (pin "A") (pinfunction "A_A") (pintype "passive"))
      (node (ref "D10") (pin "A") (pinfunction "A_A") (pintype "passive"))
      (node (ref "D11") (pin "A") (pinfunction "A_A") (pintype "passive"))
      (node (ref "D12") (pin "A") (pinfunction "A_A") (pintype "passive"))
      (node (ref "D14") (pin "A") (pinfunction "A_A") (pintype "passive"))
      (node (ref "D16") (pin "A") (pinfunction "A_A") (pintype "passive"))
      (node (ref "D18") (pin "A") (pinfunction "A_A") (pintype "passive"))
      (node (ref "D2") (pin "A") (pinfunction "A_A") (pintype "passive"))
      (node (ref "D20") (pin "A") (pinfunction "A_A") (pintype "passive"))
      (node (ref "D22") (pin "A") (pinfunction "A_A") (pintype "passive"))
      (node (ref "D25") (pin "A") (pinfunction "A_A") (pintype "passive"))
      (node (ref "D26") (pin "A") (pinfunction "A_A") (pintype "passive"))
      (node (ref "D27") (pin "A") (pinfunction "A_A") (pintype "passive"))
      (node (ref "D32") (pin "A") (pinfunction "A_A") (pintype "passive"))
      (node (ref "D4") (pin "A") (pinfunction "A_A") (pintype "passive"))
      (node (ref "D6") (pin "A") (pinfunction "A_A") (pintype "passive"))
      (node (ref "D7") (pin "A") (pinfunction "A_A") (pintype "passive"))
      (node (ref "D9") (pin "A") (pinfunction "A_A") (pintype "passive"))
      (node (ref "IC1") (pin "8") (pinfunction "VSS_8") (pintype "power_in"))
      (node (ref "IC10") (pin "4") (pinfunction "V-_4") (pintype "power_in"))
      (node (ref "IC2") (pin "4") (pinfunction "V-_4") (pintype "power_in"))
      (node (ref "IC6") (pin "7") (pinfunction "GND_7") (pintype "power_in"))
      (node (ref "IC7") (pin "6") (pinfunction "INH_6") (pintype "input"))
      (node (ref "IC7") (pin "7") (pinfunction "VEE_7") (pintype "power_in"))
      (node (ref "IC7") (pin "8") (pinfunction "GND_8") (pintype "power_in"))
      (node (ref "IC8") (pin "1") (pinfunction "A0_1") (pintype "input"))
      (node (ref "IC8") (pin "2") (pinfunction "A1_2") (pintype "input"))
      (node (ref "IC8") (pin "3") (pinfunction "A2_3") (pintype "input"))
      (node (ref "IC8") (pin "4") (pinfunction "GND_4") (pintype "power_in"))
      (node (ref "IC9") (pin "4") (pinfunction "V-_4") (pintype "power_in"))
      (node (ref "Q1") (pin "3") (pinfunction "E_3") (pintype "passive"))
      (node (ref "Q10") (pin "3") (pinfunction "E_3") (pintype "passive"))
      (node (ref "Q11") (pin "3") (pinfunction "E_3") (pintype "passive"))
      (node (ref "Q13") (pin "3") (pinfunction "E_3") (pintype "passive"))
      (node (ref "Q15") (pin "3") (pinfunction "E_3") (pintype "passive"))
      (node (ref "Q16") (pin "3") (pinfunction "E_3") (pintype "passive"))
      (node (ref "Q17") (pin "3") (pinfunction "E_3") (pintype "passive"))
      (node (ref "Q2") (pin "E") (pinfunction "E_E") (pintype "passive"))
      (node (ref "Q3") (pin "3") (pinfunction "E_3") (pintype "passive"))
      (node (ref "Q5") (pin "3") (pinfunction "E_3") (pintype "passive"))
      (node (ref "Q7") (pin "3") (pinfunction "E_3") (pintype "passive"))
      (node (ref "Q9") (pin "3") (pinfunction "E_3") (pintype "passive"))
      (node (ref "R2") (pin "1") (pinfunction "1_1") (pintype "passive"))
      (node (ref "R26") (pin "2") (pinfunction "2_2") (pintype "passive"))
      (node (ref "R29") (pin "2") (pinfunction "2_2") (pintype "passive"))
      (node (ref "R8") (pin "1") (pinfunction "1_1") (pintype "passive"))
      (node (ref "SJ1") (pin "2") (pinfunction "2_2") (pintype "passive"))
      (node (ref "SV1") (pin "1") (pinfunction "1_1") (pintype "passive"))
      (node (ref "SV2") (pin "1") (pinfunction "1_1") (pintype "passive"))
      (node (ref "SV3") (pin "1") (pinfunction "1_1") (pintype "passive"))
      (node (ref "SV3") (pin "2") (pinfunction "2_2") (pintype "passive"))
      (node (ref "U$1") (pin "IN-") (pinfunction "IN-_IN-") (pintype "bidirectional"))
      (node (ref "U$1") (pin "OUT-") (pinfunction "OUT-_OUT-") (pintype "bidirectional"))
      (node (ref "U$2") (pin "GND_1") (pinfunction "GND_GND_1") (pintype "bidirectional"))
      (node (ref "U$2") (pin "GND_2") (pinfunction "GND_GND_2") (pintype "bidirectional"))
      (node (ref "U$2") (pin "GND_3") (pinfunction "GND_GND_3") (pintype "power_in"))
      (node (ref "X1") (pin "15") (pinfunction "15_15") (pintype "passive"))
      (node (ref "X1") (pin "23") (pinfunction "23_23") (pintype "passive"))
      (node (ref "X1") (pin "26") (pinfunction "26_26") (pintype "passive"))
      (node (ref "X1") (pin "28") (pinfunction "28_28") (pintype "passive"))
      (node (ref "X1") (pin "34") (pinfunction "34_34") (pintype "passive"))
    )
    (net (code "68") (name "Net-(IC1A-O)") (class "Default")
      (node (ref "IC1") (pin "2") (pinfunction "O_2") (pintype "output"))
      (node (ref "Q1") (pin "1") (pinfunction "B_1") (pintype "passive"))
    )
    (net (code "69") (name "Net-(IC1B-O)") (class "Default")
      (node (ref "IC1") (pin "4") (pinfunction "O_4") (pintype "output"))
      (node (ref "Q7") (pin "1") (pinfunction "B_1") (pintype "passive"))
    )
    (net (code "70") (name "Net-(IC1C-O)") (class "Default")
      (node (ref "IC1") (pin "6") (pinfunction "O_6") (pintype "output"))
      (node (ref "Q3") (pin "1") (pinfunction "B_1") (pintype "passive"))
    )
    (net (code "71") (name "Net-(IC1D-O)") (class "Default")
      (node (ref "IC1") (pin "10") (pinfunction "O_10") (pintype "output"))
      (node (ref "Q13") (pin "1") (pinfunction "B_1") (pintype "passive"))
    )
    (net (code "72") (name "Net-(IC1E-O)") (class "Default")
      (node (ref "IC1") (pin "12") (pinfunction "O_12") (pintype "output"))
      (node (ref "Q5") (pin "1") (pinfunction "B_1") (pintype "passive"))
    )
    (net (code "73") (name "Net-(IC1F-O)") (class "Default")
      (node (ref "IC1") (pin "15") (pinfunction "O_15") (pintype "output"))
      (node (ref "Q11") (pin "1") (pinfunction "B_1") (pintype "passive"))
    )
    (net (code "74") (name "Net-(IC2A-+IN)") (class "Default")
      (node (ref "IC2") (pin "3") (pinfunction "+IN_3") (pintype "input"))
      (node (ref "R1") (pin "2") (pinfunction "2_2") (pintype "passive"))
      (node (ref "R2") (pin "2") (pinfunction "2_2") (pintype "passive"))
    )
    (net (code "75") (name "Net-(IC8-WP)") (class "Default")
      (node (ref "IC8") (pin "7") (pinfunction "WP_7") (pintype "input"))
      (node (ref "SJ1") (pin "1") (pinfunction "1_1") (pintype "passive"))
    )
    (net (code "76") (name "Net-(IC9A-+IN)") (class "Default")
      (node (ref "C16") (pin "1") (pinfunction "1_1") (pintype "passive"))
      (node (ref "IC9") (pin "3") (pinfunction "+IN_3") (pintype "input"))
      (node (ref "R25") (pin "2") (pinfunction "2_2") (pintype "passive"))
    )
    (net (code "77") (name "Net-(IC9A--IN)") (class "Default")
      (node (ref "IC9") (pin "2") (pinfunction "-IN_2") (pintype "input"))
      (node (ref "R26") (pin "1") (pinfunction "1_1") (pintype "passive"))
      (node (ref "R27") (pin "1") (pinfunction "1_1") (pintype "passive"))
    )
    (net (code "78") (name "Net-(IC10A-+IN)") (class "Default")
      (node (ref "C18") (pin "1") (pinfunction "1_1") (pintype "passive"))
      (node (ref "IC10") (pin "3") (pinfunction "+IN_3") (pintype "input"))
      (node (ref "R28") (pin "2") (pinfunction "2_2") (pintype "passive"))
    )
    (net (code "79") (name "Net-(IC10A--IN)") (class "Default")
      (node (ref "IC10") (pin "2") (pinfunction "-IN_2") (pintype "input"))
      (node (ref "R29") (pin "1") (pinfunction "1_1") (pintype "passive"))
      (node (ref "R30") (pin "1") (pinfunction "1_1") (pintype "passive"))
    )
    (net (code "80") (name "Net-(Q2-PadB)") (class "Default")
      (node (ref "Q2") (pin "B") (pinfunction "B_B") (pintype "passive"))
      (node (ref "R3") (pin "2") (pinfunction "2_2") (pintype "passive"))
    )
    (net (code "81") (name "Net-(Q9-B)") (class "Default")
      (node (ref "Q9") (pin "1") (pinfunction "B_1") (pintype "passive"))
      (node (ref "R16") (pin "2") (pinfunction "2_2") (pintype "passive"))
    )
    (net (code "82") (name "Net-(Q10-B)") (class "Default")
      (node (ref "Q10") (pin "1") (pinfunction "B_1") (pintype "passive"))
      (node (ref "R17") (pin "2") (pinfunction "2_2") (pintype "passive"))
    )
    (net (code "83") (name "Net-(Q15-B)") (class "Default")
      (node (ref "Q15") (pin "1") (pinfunction "B_1") (pintype "passive"))
      (node (ref "R20") (pin "2") (pinfunction "2_2") (pintype "passive"))
    )
    (net (code "84") (name "Net-(Q16-B)") (class "Default")
      (node (ref "Q16") (pin "1") (pinfunction "B_1") (pintype "passive"))
      (node (ref "R23") (pin "2") (pinfunction "2_2") (pintype "passive"))
    )
    (net (code "85") (name "Net-(Q17-B)") (class "Default")
      (node (ref "Q17") (pin "1") (pinfunction "B_1") (pintype "passive"))
      (node (ref "R21") (pin "2") (pinfunction "2_2") (pintype "passive"))
    )
    (net (code "86") (name "unconnected-(U$2-3.3V-Pad3.3V_2)") (class "Default")
      (node (ref "U$2") (pin "3.3V_2") (pinfunction "3.3V_3.3V_2") (pintype "bidirectional"))
    )
    (net (code "87") (name "unconnected-(U$2-PadPA_2)") (class "Default")
      (node (ref "U$2") (pin "PA_2") (pinfunction "PA_2_PA_2") (pintype "bidirectional"))
    )
    (net (code "88") (name "unconnected-(U$2-PadPA_3)") (class "Default")
      (node (ref "U$2") (pin "PA_3") (pinfunction "PA_3_PA_3") (pintype "bidirectional"))
    )
    (net (code "89") (name "unconnected-(U$2-PadPA_9)") (class "Default")
      (node (ref "U$2") (pin "PA_9") (pinfunction "PA_9_PA_9") (pintype "bidirectional"))
    )
    (net (code "90") (name "unconnected-(U$2-PadPA_10)") (class "Default")
      (node (ref "U$2") (pin "PA_10") (pinfunction "PA_10_PA_10") (pintype "bidirectional"))
    )
    (net (code "91") (name "unconnected-(U$2-PadPA_11)") (class "Default")
      (node (ref "U$2") (pin "PA_11") (pinfunction "PA_11_PA_11") (pintype "bidirectional"))
    )
    (net (code "92") (name "unconnected-(U$2-PadPA_12)") (class "Default")
      (node (ref "U$2") (pin "PA_12") (pinfunction "PA_12_PA_12") (pintype "bidirectional"))
    )
    (net (code "93") (name "unconnected-(U$2-PadPB_7)") (class "Default")
      (node (ref "U$2") (pin "PB_7") (pinfunction "PB_7_PB_7") (pintype "bidirectional"))
    )
    (net (code "94") (name "unconnected-(U$2-PadPB_8)") (class "Default")
      (node (ref "U$2") (pin "PB_8") (pinfunction "PB_8_PB_8") (pintype "bidirectional"))
    )
    (net (code "95") (name "unconnected-(U$2-PadPB_9)") (class "Default")
      (node (ref "U$2") (pin "PB_9") (pinfunction "PB_9_PB_9") (pintype "bidirectional"))
    )
    (net (code "96") (name "unconnected-(U$2-PadPC_13)") (class "Default")
      (node (ref "U$2") (pin "PC_13") (pinfunction "PC_13_PC_13") (pintype "bidirectional"))
    )
    (net (code "97") (name "unconnected-(U$2-PadPC_14)") (class "Default")
      (node (ref "U$2") (pin "PC_14") (pinfunction "PC_14_PC_14") (pintype "bidirectional"))
    )
    (net (code "98") (name "unconnected-(U$2-PadPC_15)") (class "Default")
      (node (ref "U$2") (pin "PC_15") (pinfunction "PC_15_PC_15") (pintype "bidirectional"))
    )
    (net (code "99") (name "unconnected-(U$2-PadRESET)") (class "Default")
      (node (ref "U$2") (pin "RESET") (pinfunction "RESET_RESET") (pintype "bidirectional"))
    )
    (net (code "100") (name "unconnected-(U$2-PadVB)") (class "Default")
      (node (ref "U$2") (pin "VB") (pinfunction "VB_VB") (pintype "bidirectional"))
    )
  )
)
